# MCU.net
KiCad netlist of a schematic drawn in Altium Designer
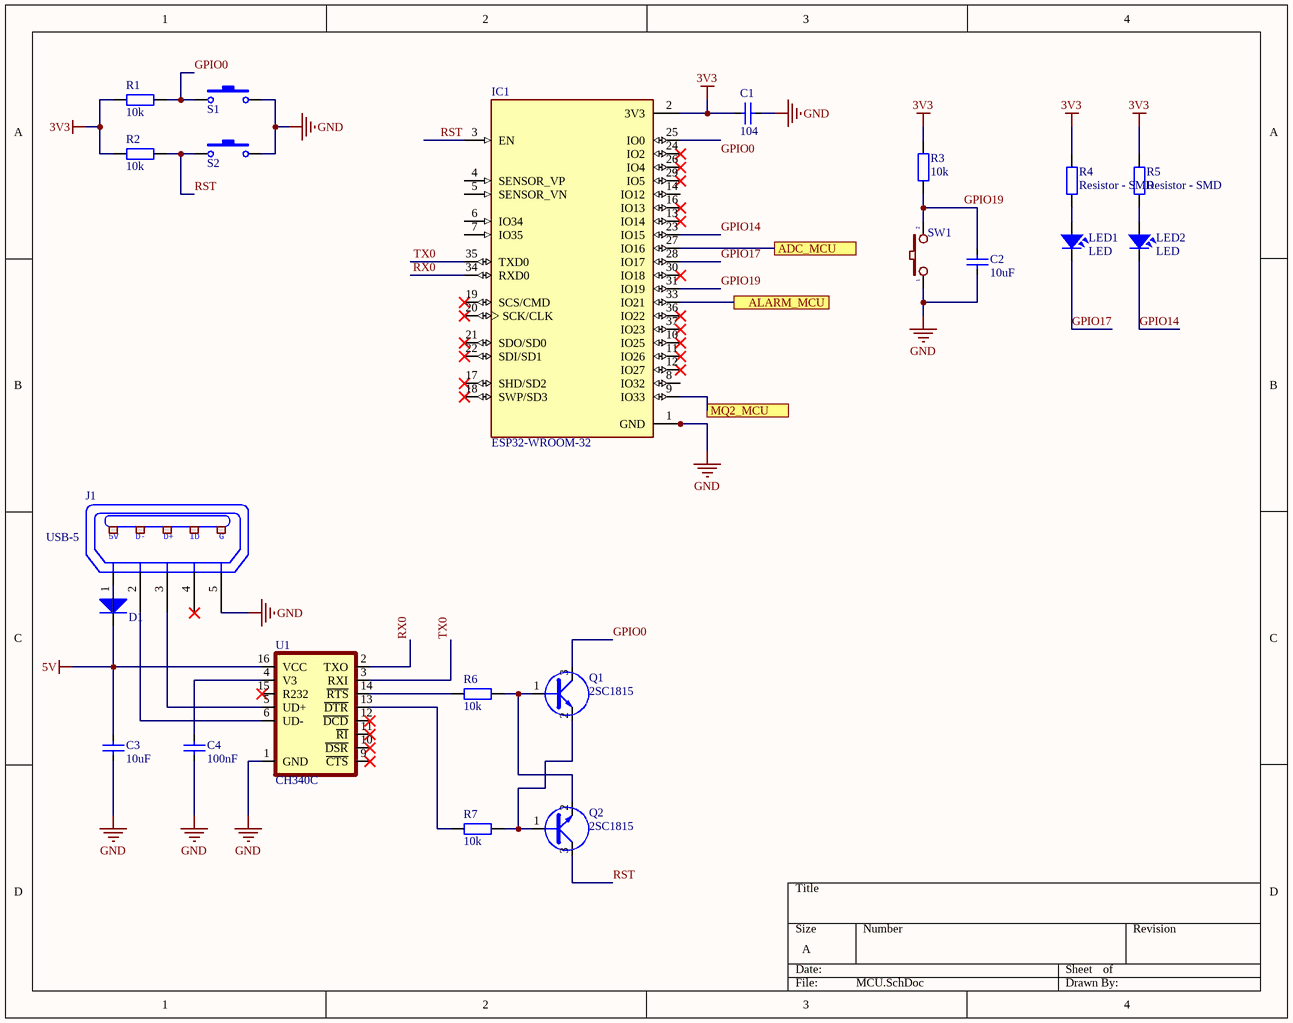
[diagram p0: MCU.SchDoc]

(export (version "E")
  (design (tool "Eeschema 10.0.6"))
  (components
    (comp (ref "C1")
      (value "104")
      (footprint "CAP_0805")
      (description "Capacitor")
      (fields (field (name "PUBLISHER") "Altium Limited"))
      (libsource (lib "My Library") (part "CapSMD"))
    )
    (comp (ref "C2")
      (value "10uF")
      (footprint "CAP_0805")
      (description "Capacitor")
      (fields (field (name "PUBLISHER") "Altium Limited"))
      (libsource (lib "My Library") (part "CapSMD"))
    )
    (comp (ref "C3")
      (value "10uF")
      (footprint "CAP_0805")
      (description "Capacitor")
      (fields (field (name "PUBLISHER") "Altium Limited"))
      (libsource (lib "My Library") (part "CapSMD"))
    )
    (comp (ref "C4")
      (value "100nF")
      (footprint "CAP_0805")
      (description "Capacitor")
      (fields (field (name "PUBLISHER") "Altium Limited"))
      (libsource (lib "My Library") (part "CapSMD"))
    )
    (comp (ref "D1")
      (value "Diode SMD")
      (footprint "DIO-214AC(SMA)")
      (description "Default Diode")
      (fields (field (name "PUBLISHER") "Altium Limited"))
      (libsource (lib "My Library") (part "Diode SMD"))
    )
    (comp (ref "IC1")
      (value "ESP32-WROOM-32")
      (footprint "MODULE_ESP32-WROOM-32")
      (description "Bluetooth, WiFi Transceiver Module 2.4GHz ~ 2.5GHz Surface Mount")
      (fields (field (name "MF") "Espressif Systems") (field (name "DIGI-KEY_PART_NUMBER") "1904-1010-1-ND"))
      (libsource (lib "My Library") (part "ESP32-WROOM-32"))
    )
    (comp (ref "J1")
      (value "USB-5")
      (footprint "USB-M1")
      (fields
        (field (name "MANUFACTURER") "FCI")
        (field (name "MANUFACTURER PART NUMBER") "10118193-0001LF")
        (field (name ".CREATOR") "MM")
        (field (name ".CHECKED PCB") "RF")
        (field (name ".CHECKED SCH") "MM")
      )
      (libsource (lib "My Library") (part "USB-5"))
    )
    (comp (ref "LED1")
      (value "LED")
      (footprint "LED-0805-Blue")
      (description "LED Single colour Green and Red")
      (libsource (lib "My Library") (part "LED"))
    )
    (comp (ref "LED2")
      (value "LED")
      (footprint "LED-3")
      (description "LED Single colour Green and Red")
      (libsource (lib "My Library") (part "LED"))
    )
    (comp (ref "Q1")
      (value "2SC1815")
      (footprint "SOT23D")
      (description "NPN 600mW, ECB")
      (libsource (lib "") (part "C1815_1"))
    )
    (comp (ref "Q2")
      (value "2SC1815")
      (footprint "SOT23D")
      (description "NPN 600mW, ECB")
      (libsource (lib "My Library") (part "C1815"))
    )
    (comp (ref "R1")
      (value "10k")
      (footprint "RES-SMD-0805")
      (description "Resistor SMD")
      (fields
        (field (name "MANUFACTURER") "Generic Components")
        (field (name "PUBLISHER") "Altium Hobart Technology Centre")
      )
      (libsource (lib "My Library") (part "Resistor - SMD"))
    )
    (comp (ref "R2")
      (value "10k")
      (footprint "RES-SMD-0805")
      (description "Resistor SMD")
      (fields
        (field (name "MANUFACTURER") "Generic Components")
        (field (name "PUBLISHER") "Altium Hobart Technology Centre")
      )
      (libsource (lib "My Library") (part "Resistor - SMD"))
    )
    (comp (ref "R3")
      (value "10k")
      (footprint "RES-SMD-0805")
      (description "Resistor SMD")
      (fields
        (field (name "MANUFACTURER") "Generic Components")
        (field (name "PUBLISHER") "Altium Hobart Technology Centre")
      )
      (libsource (lib "My Library") (part "Resistor - SMD"))
    )
    (comp (ref "R4")
      (value "Resistor - SMD")
      (footprint "RES-SMD-0805")
      (description "Resistor SMD")
      (fields
        (field (name "MANUFACTURER") "Generic Components")
        (field (name "PUBLISHER") "Altium Hobart Technology Centre")
      )
      (libsource (lib "My Library") (part "Resistor - SMD"))
    )
    (comp (ref "R5")
      (value "Resistor - SMD")
      (footprint "RES-SMD-0805")
      (description "Resistor SMD")
      (fields
        (field (name "MANUFACTURER") "Generic Components")
        (field (name "PUBLISHER") "Altium Hobart Technology Centre")
      )
      (libsource (lib "My Library") (part "Resistor - SMD"))
    )
    (comp (ref "R6")
      (value "10k")
      (footprint "RES-SMD-0805")
      (description "Resistor SMD")
      (fields
        (field (name "MANUFACTURER") "Generic Components")
        (field (name "PUBLISHER") "Altium Hobart Technology Centre")
      )
      (libsource (lib "My Library") (part "Resistor - SMD"))
    )
    (comp (ref "R7")
      (value "10k")
      (footprint "RES-SMD-0805")
      (description "Resistor SMD")
      (fields
        (field (name "MANUFACTURER") "Generic Components")
        (field (name "PUBLISHER") "Altium Hobart Technology Centre")
      )
      (libsource (lib "My Library") (part "Resistor - SMD"))
    )
    (comp (ref "S1")
      (value "SW-SMD")
      (footprint "SW 3x2x4")
      (description "Switch")
      (fields (field (name "PUBLISHER") "Altium Limited"))
      (libsource (lib "My Library") (part "SW-SMD"))
    )
    (comp (ref "S2")
      (value "SW-SMD")
      (footprint "SW 3x2x4")
      (description "Switch")
      (fields (field (name "PUBLISHER") "Altium Limited"))
      (libsource (lib "My Library") (part "SW-SMD"))
    )
    (comp (ref "SW1")
      (value "SW")
      (footprint "SW2")
      (description "Switch button 2 pin")
      (libsource (lib "My Library") (part "SW2"))
    )
    (comp (ref "U1")
      (value "CH340C")
      (footprint "SOP-16")
      (description "USB to serial chip CH340")
      (fields (field (name "MF") "WCH"))
      (libsource (lib "My Library") (part "CH340C"))
    )
  )
  (nets
    (net (code "1") (name "/ADC_MCU") (class "Default")
      (node (ref "IC1") (pin "27") (pinfunction "IO16_27") (pintype "bidirectional"))
    )
    (net (code "2") (name "/ALARM_MCU") (class "Default")
      (node (ref "IC1") (pin "33") (pinfunction "IO21_33") (pintype "bidirectional"))
    )
    (net (code "3") (name "/GPIO0") (class "Default")
      (node (ref "IC1") (pin "25") (pinfunction "IO0_25") (pintype "bidirectional"))
      (node (ref "Q1") (pin "3") (pinfunction "C_3") (pintype "passive"))
      (node (ref "R1") (pin "1") (pinfunction "1_1") (pintype "passive"))
      (node (ref "S1") (pin "1") (pinfunction "1_1") (pintype "passive"))
    )
    (net (code "4") (name "/GPIO14") (class "Default")
      (node (ref "IC1") (pin "23") (pinfunction "IO15_23") (pintype "bidirectional"))
      (node (ref "LED2") (pin "2") (pinfunction "2_2") (pintype "passive"))
    )
    (net (code "5") (name "/GPIO17") (class "Default")
      (node (ref "IC1") (pin "28") (pinfunction "IO17_28") (pintype "bidirectional"))
      (node (ref "LED1") (pin "2") (pinfunction "2_2") (pintype "passive"))
    )
    (net (code "6") (name "/GPIO19") (class "Default")
      (node (ref "C2") (pin "2") (pinfunction "2_2") (pintype "passive"))
      (node (ref "IC1") (pin "31") (pinfunction "IO19_31") (pintype "bidirectional"))
      (node (ref "R3") (pin "2") (pinfunction "2_2") (pintype "passive"))
      (node (ref "SW1") (pin "2") (pinfunction "2_2") (pintype "passive"))
    )
    (net (code "7") (name "/MQ2_MCU") (class "Default")
      (node (ref "IC1") (pin "9") (pinfunction "IO33_9") (pintype "bidirectional"))
    )
    (net (code "8") (name "/RST") (class "Default")
      (node (ref "IC1") (pin "3") (pinfunction "EN_3") (pintype "input"))
      (node (ref "Q2") (pin "3") (pinfunction "C_3") (pintype "passive"))
      (node (ref "R2") (pin "1") (pinfunction "1_1") (pintype "passive"))
      (node (ref "S2") (pin "1") (pinfunction "1_1") (pintype "passive"))
    )
    (net (code "9") (name "/RX0") (class "Default")
      (node (ref "IC1") (pin "34") (pinfunction "RXD0_34") (pintype "bidirectional"))
      (node (ref "U1") (pin "2") (pinfunction "TXO_2") (pintype "bidirectional"))
    )
    (net (code "10") (name "/TX0") (class "Default")
      (node (ref "IC1") (pin "35") (pinfunction "TXD0_35") (pintype "bidirectional"))
      (node (ref "U1") (pin "3") (pinfunction "RXI_3") (pintype "bidirectional"))
    )
    (net (code "11") (name "3V3") (class "Default")
      (node (ref "C1") (pin "1") (pinfunction "1_1") (pintype "passive"))
      (node (ref "IC1") (pin "2") (pinfunction "3V3_2") (pintype "power_in"))
      (node (ref "R1") (pin "2") (pinfunction "2_2") (pintype "passive"))
      (node (ref "R2") (pin "2") (pinfunction "2_2") (pintype "passive"))
      (node (ref "R3") (pin "1") (pinfunction "1_1") (pintype "passive"))
      (node (ref "R4") (pin "2") (pinfunction "2_2") (pintype "passive"))
      (node (ref "R5") (pin "2") (pinfunction "2_2") (pintype "passive"))
    )
    (net (code "12") (name "5V") (class "Default")
      (node (ref "C3") (pin "2") (pinfunction "2_2") (pintype "passive"))
      (node (ref "D1") (pin "2") (pinfunction "K_2") (pintype "passive"))
      (node (ref "U1") (pin "16") (pinfunction "VCC_16") (pintype "bidirectional"))
    )
    (net (code "13") (name "GND") (class "Default")
      (node (ref "C1") (pin "2") (pinfunction "2_2") (pintype "passive"))
      (node (ref "C2") (pin "1") (pinfunction "1_1") (pintype "passive"))
      (node (ref "C3") (pin "1") (pinfunction "1_1") (pintype "passive"))
      (node (ref "C4") (pin "1") (pinfunction "1_1") (pintype "passive"))
      (node (ref "IC1") (pin "1") (pinfunction "GND_1") (pintype "power_in"))
      (node (ref "IC1") (pin "15") (pinfunction "GND_15") (pintype "power_in"))
      (node (ref "IC1") (pin "38") (pinfunction "GND_38") (pintype "power_in"))
      (node (ref "IC1") (pin "39_1") (pinfunction "GND_39_1") (pintype "power_in"))
      (node (ref "IC1") (pin "39_10") (pinfunction "GND_39_10") (pintype "power_in"))
      (node (ref "IC1") (pin "39_11") (pinfunction "GND_39_11") (pintype "power_in"))
      (node (ref "IC1") (pin "39_12") (pinfunction "GND_39_12") (pintype "power_in"))
      (node (ref "IC1") (pin "39_13") (pinfunction "GND_39_13") (pintype "power_in"))
      (node (ref "IC1") (pin "39_14") (pinfunction "GND_39_14") (pintype "power_in"))
      (node (ref "IC1") (pin "39_15") (pinfunction "GND_39_15") (pintype "power_in"))
      (node (ref "IC1") (pin "39_16") (pinfunction "GND_39_16") (pintype "power_in"))
      (node (ref "IC1") (pin "39_17") (pinfunction "GND_39_17") (pintype "power_in"))
      (node (ref "IC1") (pin "39_18") (pinfunction "GND_39_18") (pintype "power_in"))
      (node (ref "IC1") (pin "39_19") (pinfunction "GND_39_19") (pintype "power_in"))
      (node (ref "IC1") (pin "39_2") (pinfunction "GND_39_2") (pintype "power_in"))
      (node (ref "IC1") (pin "39_20") (pinfunction "GND_39_20") (pintype "power_in"))
      (node (ref "IC1") (pin "39_21") (pinfunction "GND_39_21") (pintype "power_in"))
      (node (ref "IC1") (pin "39_3") (pinfunction "GND_39_3") (pintype "power_in"))
      (node (ref "IC1") (pin "39_4") (pinfunction "GND_39_4") (pintype "power_in"))
      (node (ref "IC1") (pin "39_5") (pinfunction "GND_39_5") (pintype "power_in"))
      (node (ref "IC1") (pin "39_6") (pinfunction "GND_39_6") (pintype "power_in"))
      (node (ref "IC1") (pin "39_7") (pinfunction "GND_39_7") (pintype "power_in"))
      (node (ref "IC1") (pin "39_8") (pinfunction "GND_39_8") (pintype "power_in"))
      (node (ref "IC1") (pin "39_9") (pinfunction "GND_39_9") (pintype "power_in"))
      (node (ref "J1") (pin "5") (pinfunction "P5_5") (pintype "passive"))
      (node (ref "S1") (pin "2") (pinfunction "2_2") (pintype "passive"))
      (node (ref "S2") (pin "2") (pinfunction "2_2") (pintype "passive"))
      (node (ref "SW1") (pin "1") (pinfunction "1_1") (pintype "passive"))
      (node (ref "U1") (pin "1") (pinfunction "GND_1") (pintype "bidirectional"))
    )
    (net (code "14") (name "Net-(D1-A)") (class "Default")
      (node (ref "D1") (pin "1") (pinfunction "A_1") (pintype "passive"))
      (node (ref "J1") (pin "1") (pinfunction "P1_1") (pintype "passive"))
    )
    (net (code "15") (name "Net-(J1-P2)") (class "Default")
      (node (ref "J1") (pin "2") (pinfunction "P2_2") (pintype "passive"))
      (node (ref "U1") (pin "6") (pinfunction "UD-_6") (pintype "bidirectional"))
    )
    (net (code "16") (name "Net-(J1-P3)") (class "Default")
      (node (ref "J1") (pin "3") (pinfunction "P3_3") (pintype "passive"))
      (node (ref "U1") (pin "5") (pinfunction "UD+_5") (pintype "bidirectional"))
    )
    (net (code "17") (name "Net-(LED1-Pad1)") (class "Default")
      (node (ref "LED1") (pin "1") (pinfunction "1_1") (pintype "passive"))
      (node (ref "R4") (pin "1") (pinfunction "1_1") (pintype "passive"))
    )
    (net (code "18") (name "Net-(LED2-Pad1)") (class "Default")
      (node (ref "LED2") (pin "1") (pinfunction "1_1") (pintype "passive"))
      (node (ref "R5") (pin "1") (pinfunction "1_1") (pintype "passive"))
    )
    (net (code "19") (name "Net-(Q1-B)") (class "Default")
      (node (ref "Q1") (pin "1") (pinfunction "B_1") (pintype "passive"))
      (node (ref "Q2") (pin "2") (pinfunction "E_2") (pintype "passive"))
      (node (ref "R6") (pin "1") (pinfunction "1_1") (pintype "passive"))
    )
    (net (code "20") (name "Net-(Q1-E)") (class "Default")
      (node (ref "Q1") (pin "2") (pinfunction "E_2") (pintype "passive"))
      (node (ref "Q2") (pin "1") (pinfunction "B_1") (pintype "passive"))
      (node (ref "R7") (pin "1") (pinfunction "1_1") (pintype "passive"))
    )
    (net (code "21") (name "Net-(U1-V3)") (class "Default")
      (node (ref "C4") (pin "2") (pinfunction "2_2") (pintype "passive"))
      (node (ref "U1") (pin "4") (pinfunction "V3_4") (pintype "bidirectional"))
    )
    (net (code "22") (name "Net-(U1-~{DTR})") (class "Default")
      (node (ref "R7") (pin "2") (pinfunction "2_2") (pintype "passive"))
      (node (ref "U1") (pin "13") (pinfunction "~{DTR}_13") (pintype "bidirectional"))
    )
    (net (code "23") (name "Net-(U1-~{RTS})") (class "Default")
      (node (ref "R6") (pin "2") (pinfunction "2_2") (pintype "passive"))
      (node (ref "U1") (pin "14") (pinfunction "~{RTS}_14") (pintype "bidirectional"))
    )
    (net (code "24") (name "unconnected-(IC1-IO2-Pad24)") (class "Default")
      (node (ref "IC1") (pin "24") (pinfunction "IO2_24") (pintype "bidirectional+no_connect"))
    )
    (net (code "25") (name "unconnected-(IC1-IO4-Pad26)") (class "Default")
      (node (ref "IC1") (pin "26") (pinfunction "IO4_26") (pintype "bidirectional+no_connect"))
    )
    (net (code "26") (name "unconnected-(IC1-IO5-Pad29)") (class "Default")
      (node (ref "IC1") (pin "29") (pinfunction "IO5_29") (pintype "bidirectional+no_connect"))
    )
    (net (code "27") (name "unconnected-(IC1-IO12-Pad14)") (class "Default")
      (node (ref "IC1") (pin "14") (pinfunction "IO12_14") (pintype "bidirectional"))
    )
    (net (code "28") (name "unconnected-(IC1-IO13-Pad16)") (class "Default")
      (node (ref "IC1") (pin "16") (pinfunction "IO13_16") (pintype "bidirectional+no_connect"))
    )
    (net (code "29") (name "unconnected-(IC1-IO14-Pad13)") (class "Default")
      (node (ref "IC1") (pin "13") (pinfunction "IO14_13") (pintype "bidirectional+no_connect"))
    )
    (net (code "30") (name "unconnected-(IC1-IO18-Pad30)") (class "Default")
      (node (ref "IC1") (pin "30") (pinfunction "IO18_30") (pintype "bidirectional+no_connect"))
    )
    (net (code "31") (name "unconnected-(IC1-IO22-Pad36)") (class "Default")
      (node (ref "IC1") (pin "36") (pinfunction "IO22_36") (pintype "bidirectional+no_connect"))
    )
    (net (code "32") (name "unconnected-(IC1-IO23-Pad37)") (class "Default")
      (node (ref "IC1") (pin "37") (pinfunction "IO23_37") (pintype "bidirectional+no_connect"))
    )
    (net (code "33") (name "unconnected-(IC1-IO25-Pad10)") (class "Default")
      (node (ref "IC1") (pin "10") (pinfunction "IO25_10") (pintype "bidirectional+no_connect"))
    )
    (net (code "34") (name "unconnected-(IC1-IO26-Pad11)") (class "Default")
      (node (ref "IC1") (pin "11") (pinfunction "IO26_11") (pintype "bidirectional+no_connect"))
    )
    (net (code "35") (name "unconnected-(IC1-IO27-Pad12)") (class "Default")
      (node (ref "IC1") (pin "12") (pinfunction "IO27_12") (pintype "bidirectional+no_connect"))
    )
    (net (code "36") (name "unconnected-(IC1-IO32-Pad8)") (class "Default")
      (node (ref "IC1") (pin "8") (pinfunction "IO32_8") (pintype "bidirectional"))
    )
    (net (code "37") (name "unconnected-(IC1-IO34-Pad6)") (class "Default")
      (node (ref "IC1") (pin "6") (pinfunction "IO34_6") (pintype "input"))
    )
    (net (code "38") (name "unconnected-(IC1-IO35-Pad7)") (class "Default")
      (node (ref "IC1") (pin "7") (pinfunction "IO35_7") (pintype "input"))
    )
    (net (code "39") (name "unconnected-(IC1-SCK{slash}CLK-Pad20)") (class "Default")
      (node (ref "IC1") (pin "20") (pinfunction "SCK/CLK_20") (pintype "bidirectional+no_connect"))
    )
    (net (code "40") (name "unconnected-(IC1-SCS{slash}CMD-Pad19)") (class "Default")
      (node (ref "IC1") (pin "19") (pinfunction "SCS/CMD_19") (pintype "bidirectional+no_connect"))
    )
    (net (code "41") (name "unconnected-(IC1-SDI{slash}SD1-Pad22)") (class "Default")
      (node (ref "IC1") (pin "22") (pinfunction "SDI/SD1_22") (pintype "bidirectional+no_connect"))
    )
    (net (code "42") (name "unconnected-(IC1-SDO{slash}SD0-Pad21)") (class "Default")
      (node (ref "IC1") (pin "21") (pinfunction "SDO/SD0_21") (pintype "bidirectional+no_connect"))
    )
    (net (code "43") (name "unconnected-(IC1-SENSOR_VN-Pad5)") (class "Default")
      (node (ref "IC1") (pin "5") (pinfunction "SENSOR_VN_5") (pintype "input"))
    )
    (net (code "44") (name "unconnected-(IC1-SENSOR_VP-Pad4)") (class "Default")
      (node (ref "IC1") (pin "4") (pinfunction "SENSOR_VP_4") (pintype "input"))
    )
    (net (code "45") (name "unconnected-(IC1-SHD{slash}SD2-Pad17)") (class "Default")
      (node (ref "IC1") (pin "17") (pinfunction "SHD/SD2_17") (pintype "bidirectional+no_connect"))
    )
    (net (code "46") (name "unconnected-(IC1-SWP{slash}SD3-Pad18)") (class "Default")
      (node (ref "IC1") (pin "18") (pinfunction "SWP/SD3_18") (pintype "bidirectional+no_connect"))
    )
    (net (code "47") (name "unconnected-(J1-P4-Pad4)") (class "Default")
      (node (ref "J1") (pin "4") (pinfunction "P4_4") (pintype "passive+no_connect"))
    )
    (net (code "48") (name "unconnected-(U1-R232-Pad15)") (class "Default")
      (node (ref "U1") (pin "15") (pinfunction "R232_15") (pintype "bidirectional+no_connect"))
    )
    (net (code "49") (name "unconnected-(U1-~{CTS}-Pad9)") (class "Default")
      (node (ref "U1") (pin "9") (pinfunction "~{CTS}_9") (pintype "bidirectional+no_connect"))
    )
    (net (code "50") (name "unconnected-(U1-~{DCD}-Pad12)") (class "Default")
      (node (ref "U1") (pin "12") (pinfunction "~{DCD}_12") (pintype "bidirectional+no_connect"))
    )
    (net (code "51") (name "unconnected-(U1-~{DSR}-Pad10)") (class "Default")
      (node (ref "U1") (pin "10") (pinfunction "~{DSR}_10") (pintype "bidirectional+no_connect"))
    )
    (net (code "52") (name "unconnected-(U1-~{RI}-Pad11)") (class "Default")
      (node (ref "U1") (pin "11") (pinfunction "~{RI}_11") (pintype "bidirectional+no_connect"))
    )
  )
)
